# mm16.net
KiCad netlist of a schematic drawn in EAGLE
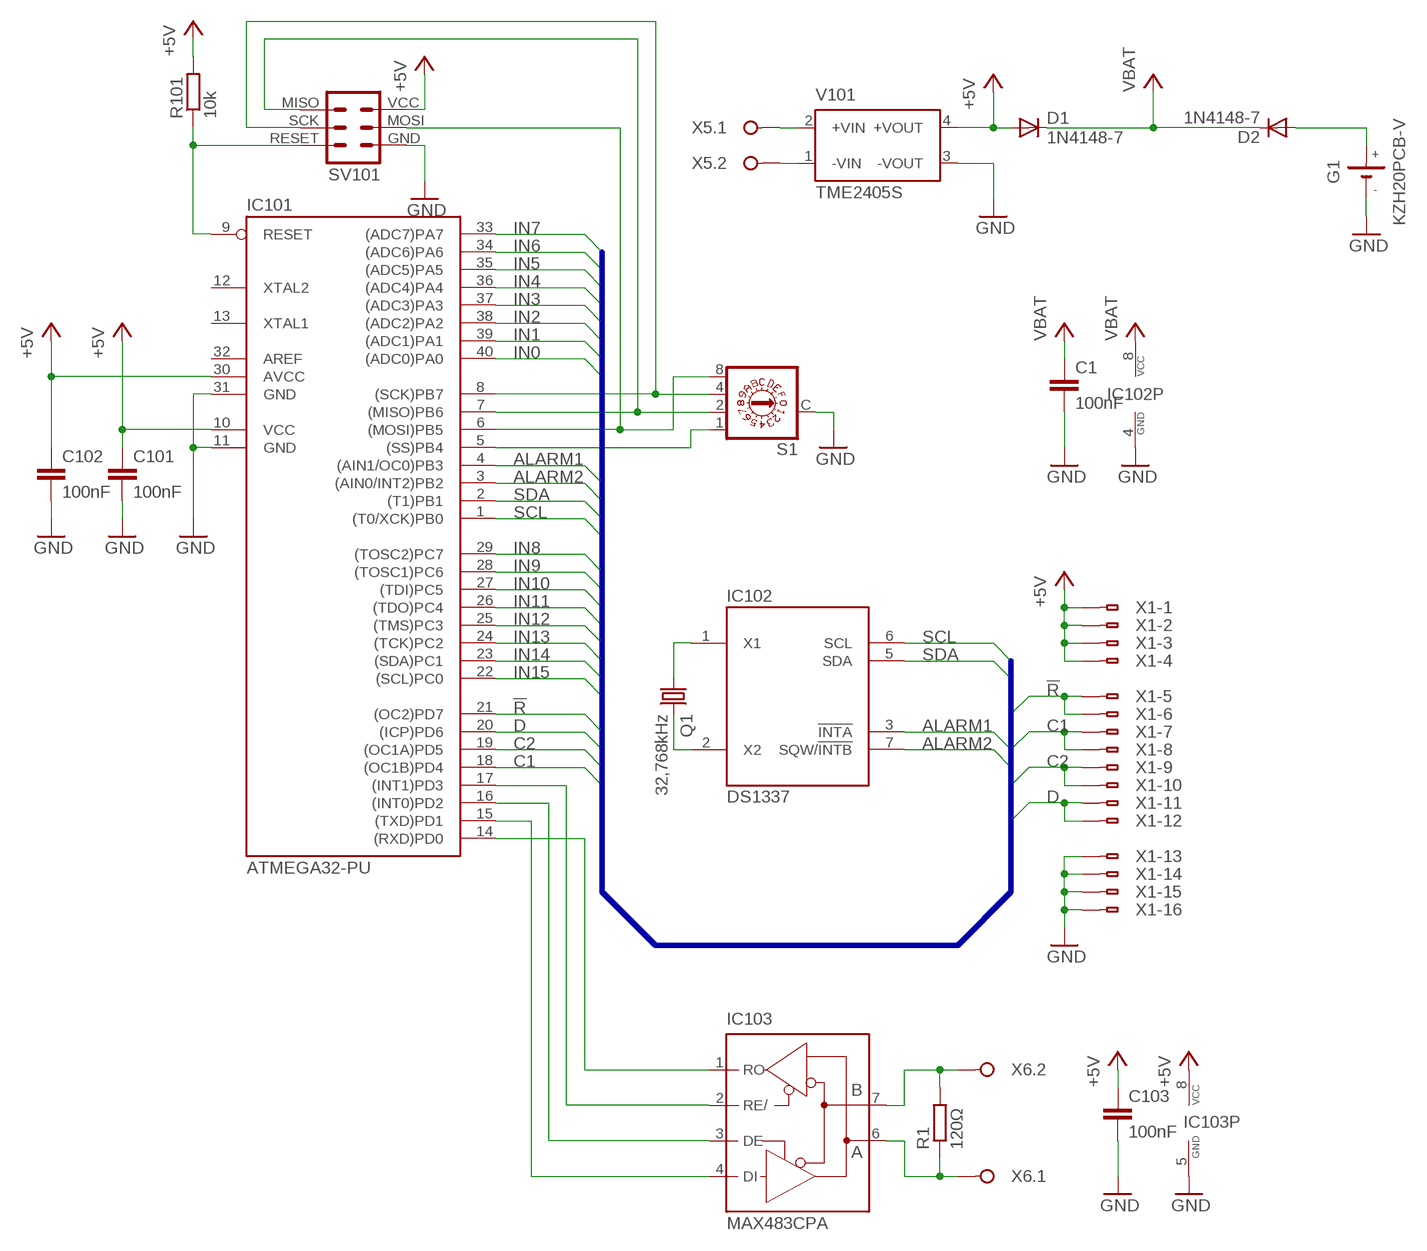
[diagram p0: schematic, sheet 1]
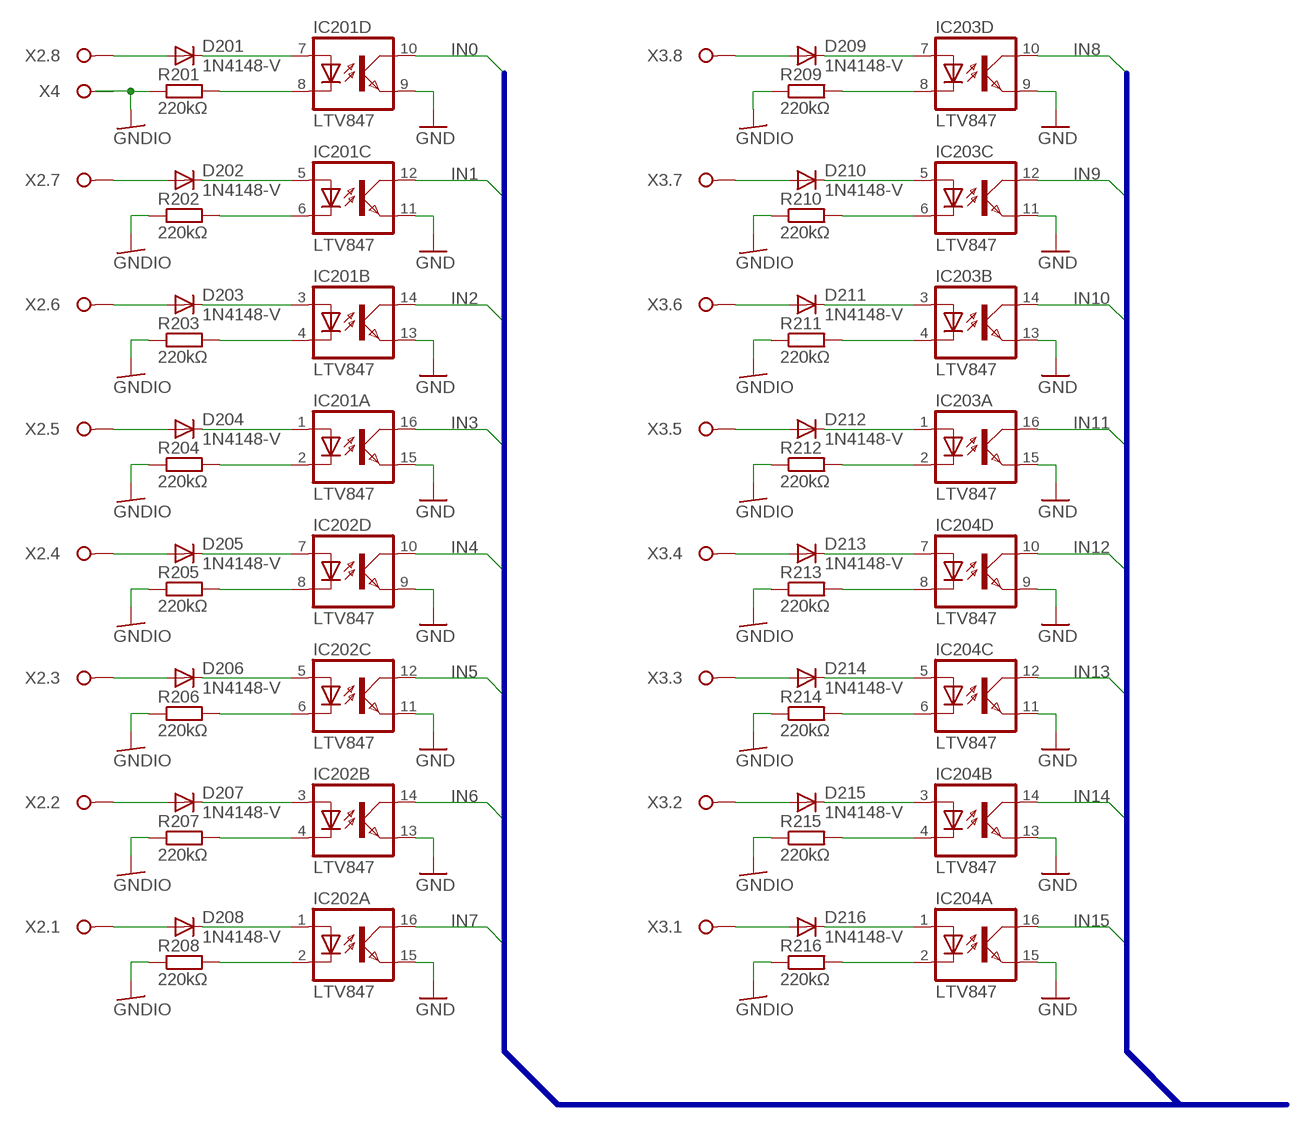
[diagram p1: schematic, sheet 2]

(export (version "E")
  (design (tool "Eeschema 10.0.6"))
  (components
    (comp (ref "D201")
      (value "1N4148-V")
      (footprint "eagle-import:DO35-V")
      (libsource (lib "eagle-import") (part "1N4148-V"))
    )
    (comp (ref "D202")
      (value "1N4148-V")
      (footprint "eagle-import:DO35-V")
      (libsource (lib "eagle-import") (part "1N4148-V"))
    )
    (comp (ref "D203")
      (value "1N4148-V")
      (footprint "eagle-import:DO35-V")
      (libsource (lib "eagle-import") (part "1N4148-V"))
    )
    (comp (ref "D204")
      (value "1N4148-V")
      (footprint "eagle-import:DO35-V")
      (libsource (lib "eagle-import") (part "1N4148-V"))
    )
    (comp (ref "D205")
      (value "1N4148-V")
      (footprint "eagle-import:DO35-V")
      (libsource (lib "eagle-import") (part "1N4148-V"))
    )
    (comp (ref "D206")
      (value "1N4148-V")
      (footprint "eagle-import:DO35-V")
      (libsource (lib "eagle-import") (part "1N4148-V"))
    )
    (comp (ref "D207")
      (value "1N4148-V")
      (footprint "eagle-import:DO35-V")
      (libsource (lib "eagle-import") (part "1N4148-V"))
    )
    (comp (ref "D208")
      (value "1N4148-V")
      (footprint "eagle-import:DO35-V")
      (libsource (lib "eagle-import") (part "1N4148-V"))
    )
    (comp (ref "D209")
      (value "1N4148-V")
      (footprint "eagle-import:DO35-V")
      (libsource (lib "eagle-import") (part "1N4148-V"))
    )
    (comp (ref "D210")
      (value "1N4148-V")
      (footprint "eagle-import:DO35-V")
      (libsource (lib "eagle-import") (part "1N4148-V"))
    )
    (comp (ref "D211")
      (value "1N4148-V")
      (footprint "eagle-import:DO35-V")
      (libsource (lib "eagle-import") (part "1N4148-V"))
    )
    (comp (ref "D212")
      (value "1N4148-V")
      (footprint "eagle-import:DO35-V")
      (libsource (lib "eagle-import") (part "1N4148-V"))
    )
    (comp (ref "D213")
      (value "1N4148-V")
      (footprint "eagle-import:DO35-V")
      (libsource (lib "eagle-import") (part "1N4148-V"))
    )
    (comp (ref "D214")
      (value "1N4148-V")
      (footprint "eagle-import:DO35-V")
      (libsource (lib "eagle-import") (part "1N4148-V"))
    )
    (comp (ref "D215")
      (value "1N4148-V")
      (footprint "eagle-import:DO35-V")
      (libsource (lib "eagle-import") (part "1N4148-V"))
    )
    (comp (ref "D216")
      (value "1N4148-V")
      (footprint "eagle-import:DO35-V")
      (libsource (lib "eagle-import") (part "1N4148-V"))
    )
    (comp (ref "IC201")
      (value "LTV847")
      (footprint "eagle-import:DIL16")
      (libsource (lib "eagle-import") (part "LTV847"))
    )
    (comp (ref "IC202")
      (value "LTV847")
      (footprint "eagle-import:DIL16")
      (libsource (lib "eagle-import") (part "LTV847"))
    )
    (comp (ref "IC203")
      (value "LTV847")
      (footprint "eagle-import:DIL16")
      (libsource (lib "eagle-import") (part "LTV847"))
    )
    (comp (ref "IC204")
      (value "LTV847")
      (footprint "eagle-import:DIL16")
      (libsource (lib "eagle-import") (part "LTV847"))
    )
    (comp (ref "R201")
      (value "220kΩ")
      (footprint "eagle-import:0204V")
      (libsource (lib "eagle-import") (part "R_0204/2V"))
    )
    (comp (ref "R202")
      (value "220kΩ")
      (footprint "eagle-import:0204V")
      (libsource (lib "eagle-import") (part "R_0204/2V"))
    )
    (comp (ref "R203")
      (value "220kΩ")
      (footprint "eagle-import:0204V")
      (libsource (lib "eagle-import") (part "R_0204/2V"))
    )
    (comp (ref "R204")
      (value "220kΩ")
      (footprint "eagle-import:0204V")
      (libsource (lib "eagle-import") (part "R_0204/2V"))
    )
    (comp (ref "R205")
      (value "220kΩ")
      (footprint "eagle-import:0204V")
      (libsource (lib "eagle-import") (part "R_0204/2V"))
    )
    (comp (ref "R206")
      (value "220kΩ")
      (footprint "eagle-import:0204V")
      (libsource (lib "eagle-import") (part "R_0204/2V"))
    )
    (comp (ref "R207")
      (value "220kΩ")
      (footprint "eagle-import:0204V")
      (libsource (lib "eagle-import") (part "R_0204/2V"))
    )
    (comp (ref "R208")
      (value "220kΩ")
      (footprint "eagle-import:0204V")
      (libsource (lib "eagle-import") (part "R_0204/2V"))
    )
    (comp (ref "R209")
      (value "220kΩ")
      (footprint "eagle-import:0204V")
      (libsource (lib "eagle-import") (part "R_0204/2V"))
    )
    (comp (ref "R210")
      (value "220kΩ")
      (footprint "eagle-import:0204V")
      (libsource (lib "eagle-import") (part "R_0204/2V"))
    )
    (comp (ref "R211")
      (value "220kΩ")
      (footprint "eagle-import:0204V")
      (libsource (lib "eagle-import") (part "R_0204/2V"))
    )
    (comp (ref "R212")
      (value "220kΩ")
      (footprint "eagle-import:0204V")
      (libsource (lib "eagle-import") (part "R_0204/2V"))
    )
    (comp (ref "R213")
      (value "220kΩ")
      (footprint "eagle-import:0204V")
      (libsource (lib "eagle-import") (part "R_0204/2V"))
    )
    (comp (ref "R214")
      (value "220kΩ")
      (footprint "eagle-import:0204V")
      (libsource (lib "eagle-import") (part "R_0204/2V"))
    )
    (comp (ref "R215")
      (value "220kΩ")
      (footprint "eagle-import:0204V")
      (libsource (lib "eagle-import") (part "R_0204/2V"))
    )
    (comp (ref "R216")
      (value "220kΩ")
      (footprint "eagle-import:0204V")
      (libsource (lib "eagle-import") (part "R_0204/2V"))
    )
    (comp (ref "X2")
      (value "WAGO_236-408")
      (footprint "eagle-import:WAGO_236-408")
      (libsource (lib "eagle-import") (part "WAGO_236-408"))
    )
    (comp (ref "X3")
      (value "WAGO_236-408")
      (footprint "eagle-import:WAGO_236-408")
      (libsource (lib "eagle-import") (part "WAGO_236-408"))
    )
    (comp (ref "X4")
      (value "WAGO_236-401")
      (footprint "eagle-import:WAGO_236-401")
      (libsource (lib "eagle-import") (part "WAGO_236-401"))
    )
    (comp (ref "C1")
      (value "100nF")
      (footprint "eagle-import:C025-025X050")
      (libsource (lib "eagle-import") (part "C_025-025X050"))
    )
    (comp (ref "C101")
      (value "100nF")
      (footprint "eagle-import:C025-025X050")
      (libsource (lib "eagle-import") (part "C_025-025X050"))
    )
    (comp (ref "C102")
      (value "100nF")
      (footprint "eagle-import:C025-025X050")
      (libsource (lib "eagle-import") (part "C_025-025X050"))
    )
    (comp (ref "C103")
      (value "100nF")
      (footprint "eagle-import:C025-025X050")
      (libsource (lib "eagle-import") (part "C_025-025X050"))
    )
    (comp (ref "D1")
      (value "1N4148-7")
      (footprint "eagle-import:DO35-7")
      (libsource (lib "eagle-import") (part "1N4148-7"))
    )
    (comp (ref "D2")
      (value "1N4148-7")
      (footprint "eagle-import:DO35-7")
      (libsource (lib "eagle-import") (part "1N4148-7"))
    )
    (comp (ref "G1")
      (value "KZH20PCB-V")
      (footprint "eagle-import:KZH20PCB-V")
      (libsource (lib "eagle-import") (part "KZH20PCB-V"))
    )
    (comp (ref "IC101")
      (value "ATMEGA32-PU")
      (footprint "eagle-import:DIL40")
      (libsource (lib "eagle-import") (part "ATMEGA32-PU"))
    )
    (comp (ref "IC102")
      (value "DS1337")
      (footprint "eagle-import:DIL08")
      (libsource (lib "eagle-import") (part "DS1337"))
    )
    (comp (ref "IC103")
      (value "MAX483CPA")
      (footprint "eagle-import:DIL08")
      (libsource (lib "eagle-import") (part "MAX48CPA3"))
    )
    (comp (ref "Q1")
      (value "32,768kHz")
      (footprint "eagle-import:TC38H")
      (libsource (lib "eagle-import") (part "Q_TC38H"))
    )
    (comp (ref "R1")
      (value "120Ω")
      (footprint "eagle-import:0204V")
      (libsource (lib "eagle-import") (part "R_0204/2V"))
    )
    (comp (ref "R101")
      (value "10k")
      (footprint "eagle-import:0204V")
      (libsource (lib "eagle-import") (part "R_0204/2V"))
    )
    (comp (ref "S1")
      (value "P103")
      (footprint "eagle-import:P103")
      (libsource (lib "eagle-import") (part "P103"))
    )
    (comp (ref "SV101")
      (value "AVR_ISP6")
      (footprint "eagle-import:ML6")
      (libsource (lib "eagle-import") (part "AVR_ISP6"))
    )
    (comp (ref "V101")
      (value "TME2405S")
      (footprint "eagle-import:TME-24V")
      (fields
        (field (name "MPN") "TME 2405S")
        (field (name "MPN_1") "TME 2405S")
        (field (name "OC_FARNELL") "1007547")
        (field (name "OC_NEWARK") "51R5329")
      )
      (libsource (lib "eagle-import") (part "TME?2405S"))
    )
    (comp (ref "X1")
      (value "WS16V")
      (footprint "eagle-import:WS16V")
      (libsource (lib "eagle-import") (part "WS16V"))
    )
    (comp (ref "X5")
      (value "WAGO_236-402")
      (footprint "eagle-import:WAGO_236-402")
      (libsource (lib "eagle-import") (part "WAGO_236-402"))
    )
    (comp (ref "X6")
      (value "WAGO_236-402")
      (footprint "eagle-import:WAGO_236-402")
      (libsource (lib "eagle-import") (part "WAGO_236-402"))
    )
  )
  (nets
    (net (code "1") (name "+5V") (class "Default")
      (node (ref "C101") (pin "1") (pinfunction "1_1") (pintype "passive"))
      (node (ref "C102") (pin "1") (pinfunction "1_1") (pintype "passive"))
      (node (ref "C103") (pin "1") (pinfunction "1_1") (pintype "passive"))
      (node (ref "D1") (pin "A") (pinfunction "A_A") (pintype "passive"))
      (node (ref "IC101") (pin "10") (pinfunction "VCC_10") (pintype "power_in"))
      (node (ref "IC101") (pin "30") (pinfunction "AVCC_30") (pintype "power_in"))
      (node (ref "IC103") (pin "8") (pinfunction "VCC_8") (pintype "power_in"))
      (node (ref "R101") (pin "2") (pinfunction "2_2") (pintype "passive"))
      (node (ref "SV101") (pin "VCC") (pinfunction "VCC_VCC") (pintype "passive"))
      (node (ref "V101") (pin "4") (pinfunction "+VOUT_4") (pintype "passive"))
      (node (ref "X1") (pin "1") (pinfunction "A_1") (pintype "passive"))
      (node (ref "X1") (pin "2") (pinfunction "A_2") (pintype "passive"))
      (node (ref "X1") (pin "3") (pinfunction "A_3") (pintype "passive"))
      (node (ref "X1") (pin "4") (pinfunction "A_4") (pintype "passive"))
    )
    (net (code "2") (name "ALARM1") (class "Default")
      (node (ref "IC101") (pin "4") (pinfunction "(AIN1/OC0)PB3_4") (pintype "bidirectional"))
      (node (ref "IC102") (pin "3") (pinfunction "~{INTA}_3") (pintype "open_collector"))
    )
    (net (code "3") (name "ALARM2") (class "Default")
      (node (ref "IC101") (pin "3") (pinfunction "(AIN0/INT2)PB2_3") (pintype "bidirectional"))
      (node (ref "IC102") (pin "7") (pinfunction "SQW/~{INTB}_7") (pintype "open_collector"))
    )
    (net (code "4") (name "C1") (class "Default")
      (node (ref "IC101") (pin "18") (pinfunction "(OC1B)PD4_18") (pintype "bidirectional"))
      (node (ref "X1") (pin "7") (pinfunction "A_7") (pintype "passive"))
      (node (ref "X1") (pin "8") (pinfunction "A_8") (pintype "passive"))
    )
    (net (code "5") (name "C2") (class "Default")
      (node (ref "IC101") (pin "19") (pinfunction "(OC1A)PD5_19") (pintype "bidirectional"))
      (node (ref "X1") (pin "10") (pinfunction "A_10") (pintype "passive"))
      (node (ref "X1") (pin "9") (pinfunction "A_9") (pintype "passive"))
    )
    (net (code "6") (name "D") (class "Default")
      (node (ref "IC101") (pin "20") (pinfunction "(ICP)PD6_20") (pintype "bidirectional"))
      (node (ref "X1") (pin "11") (pinfunction "A_11") (pintype "passive"))
      (node (ref "X1") (pin "12") (pinfunction "A_12") (pintype "passive"))
    )
    (net (code "7") (name "GND") (class "Default")
      (node (ref "C1") (pin "2") (pinfunction "2_2") (pintype "passive"))
      (node (ref "C101") (pin "2") (pinfunction "2_2") (pintype "passive"))
      (node (ref "C102") (pin "2") (pinfunction "2_2") (pintype "passive"))
      (node (ref "C103") (pin "2") (pinfunction "2_2") (pintype "passive"))
      (node (ref "G1") (pin "-") (pinfunction "-_-") (pintype "passive"))
      (node (ref "IC101") (pin "11") (pinfunction "GND_11") (pintype "power_in"))
      (node (ref "IC101") (pin "31") (pinfunction "GND_31") (pintype "power_in"))
      (node (ref "IC102") (pin "4") (pinfunction "GND_4") (pintype "power_in"))
      (node (ref "IC103") (pin "5") (pinfunction "GND_5") (pintype "power_in"))
      (node (ref "IC201") (pin "11") (pinfunction "EMIT_11") (pintype "passive"))
      (node (ref "IC201") (pin "13") (pinfunction "EMIT_13") (pintype "passive"))
      (node (ref "IC201") (pin "15") (pinfunction "EMIT_15") (pintype "passive"))
      (node (ref "IC201") (pin "9") (pinfunction "EMIT_9") (pintype "passive"))
      (node (ref "IC202") (pin "11") (pinfunction "EMIT_11") (pintype "passive"))
      (node (ref "IC202") (pin "13") (pinfunction "EMIT_13") (pintype "passive"))
      (node (ref "IC202") (pin "15") (pinfunction "EMIT_15") (pintype "passive"))
      (node (ref "IC202") (pin "9") (pinfunction "EMIT_9") (pintype "passive"))
      (node (ref "IC203") (pin "11") (pinfunction "EMIT_11") (pintype "passive"))
      (node (ref "IC203") (pin "13") (pinfunction "EMIT_13") (pintype "passive"))
      (node (ref "IC203") (pin "15") (pinfunction "EMIT_15") (pintype "passive"))
      (node (ref "IC203") (pin "9") (pinfunction "EMIT_9") (pintype "passive"))
      (node (ref "IC204") (pin "11") (pinfunction "EMIT_11") (pintype "passive"))
      (node (ref "IC204") (pin "13") (pinfunction "EMIT_13") (pintype "passive"))
      (node (ref "IC204") (pin "15") (pinfunction "EMIT_15") (pintype "passive"))
      (node (ref "IC204") (pin "9") (pinfunction "EMIT_9") (pintype "passive"))
      (node (ref "S1") (pin "C") (pinfunction "C_C") (pintype "passive"))
      (node (ref "SV101") (pin "GND") (pinfunction "GND_GND") (pintype "passive"))
      (node (ref "V101") (pin "3") (pinfunction "-VOUT_3") (pintype "passive"))
      (node (ref "X1") (pin "13") (pinfunction "A_13") (pintype "passive"))
      (node (ref "X1") (pin "14") (pinfunction "A_14") (pintype "passive"))
      (node (ref "X1") (pin "15") (pinfunction "A_15") (pintype "passive"))
      (node (ref "X1") (pin "16") (pinfunction "A_16") (pintype "passive"))
    )
    (net (code "8") (name "GNDIO") (class "Default")
      (node (ref "R201") (pin "1") (pinfunction "1_1") (pintype "passive"))
      (node (ref "R202") (pin "1") (pinfunction "1_1") (pintype "passive"))
      (node (ref "R203") (pin "1") (pinfunction "1_1") (pintype "passive"))
      (node (ref "R204") (pin "1") (pinfunction "1_1") (pintype "passive"))
      (node (ref "R205") (pin "1") (pinfunction "1_1") (pintype "passive"))
      (node (ref "R206") (pin "1") (pinfunction "1_1") (pintype "passive"))
      (node (ref "R207") (pin "1") (pinfunction "1_1") (pintype "passive"))
      (node (ref "R208") (pin "1") (pinfunction "1_1") (pintype "passive"))
      (node (ref "R209") (pin "1") (pinfunction "1_1") (pintype "passive"))
      (node (ref "R210") (pin "1") (pinfunction "1_1") (pintype "passive"))
      (node (ref "R211") (pin "1") (pinfunction "1_1") (pintype "passive"))
      (node (ref "R212") (pin "1") (pinfunction "1_1") (pintype "passive"))
      (node (ref "R213") (pin "1") (pinfunction "1_1") (pintype "passive"))
      (node (ref "R214") (pin "1") (pinfunction "1_1") (pintype "passive"))
      (node (ref "R215") (pin "1") (pinfunction "1_1") (pintype "passive"))
      (node (ref "R216") (pin "1") (pinfunction "1_1") (pintype "passive"))
      (node (ref "X4") (pin "A1") (pinfunction "A_A1") (pintype "passive"))
      (node (ref "X4") (pin "B1") (pinfunction "B_B1") (pintype "passive"))
    )
    (net (code "9") (name "IN0") (class "Default")
      (node (ref "IC101") (pin "40") (pinfunction "(ADC0)PA0_40") (pintype "bidirectional"))
      (node (ref "IC201") (pin "10") (pinfunction "COL_10") (pintype "passive"))
    )
    (net (code "10") (name "IN1") (class "Default")
      (node (ref "IC101") (pin "39") (pinfunction "(ADC1)PA1_39") (pintype "bidirectional"))
      (node (ref "IC201") (pin "12") (pinfunction "COL_12") (pintype "passive"))
    )
    (net (code "11") (name "IN2") (class "Default")
      (node (ref "IC101") (pin "38") (pinfunction "(ADC2)PA2_38") (pintype "bidirectional"))
      (node (ref "IC201") (pin "14") (pinfunction "COL_14") (pintype "passive"))
    )
    (net (code "12") (name "IN3") (class "Default")
      (node (ref "IC101") (pin "37") (pinfunction "(ADC3)PA3_37") (pintype "bidirectional"))
      (node (ref "IC201") (pin "16") (pinfunction "COL_16") (pintype "passive"))
    )
    (net (code "13") (name "IN4") (class "Default")
      (node (ref "IC101") (pin "36") (pinfunction "(ADC4)PA4_36") (pintype "bidirectional"))
      (node (ref "IC202") (pin "10") (pinfunction "COL_10") (pintype "passive"))
    )
    (net (code "14") (name "IN5") (class "Default")
      (node (ref "IC101") (pin "35") (pinfunction "(ADC5)PA5_35") (pintype "bidirectional"))
      (node (ref "IC202") (pin "12") (pinfunction "COL_12") (pintype "passive"))
    )
    (net (code "15") (name "IN6") (class "Default")
      (node (ref "IC101") (pin "34") (pinfunction "(ADC6)PA6_34") (pintype "bidirectional"))
      (node (ref "IC202") (pin "14") (pinfunction "COL_14") (pintype "passive"))
    )
    (net (code "16") (name "IN7") (class "Default")
      (node (ref "IC101") (pin "33") (pinfunction "(ADC7)PA7_33") (pintype "bidirectional"))
      (node (ref "IC202") (pin "16") (pinfunction "COL_16") (pintype "passive"))
    )
    (net (code "17") (name "IN8") (class "Default")
      (node (ref "IC101") (pin "29") (pinfunction "(TOSC2)PC7_29") (pintype "bidirectional"))
      (node (ref "IC203") (pin "10") (pinfunction "COL_10") (pintype "passive"))
    )
    (net (code "18") (name "IN9") (class "Default")
      (node (ref "IC101") (pin "28") (pinfunction "(TOSC1)PC6_28") (pintype "bidirectional"))
      (node (ref "IC203") (pin "12") (pinfunction "COL_12") (pintype "passive"))
    )
    (net (code "19") (name "IN10") (class "Default")
      (node (ref "IC101") (pin "27") (pinfunction "(TDI)PC5_27") (pintype "bidirectional"))
      (node (ref "IC203") (pin "14") (pinfunction "COL_14") (pintype "passive"))
    )
    (net (code "20") (name "IN11") (class "Default")
      (node (ref "IC101") (pin "26") (pinfunction "(TDO)PC4_26") (pintype "bidirectional"))
      (node (ref "IC203") (pin "16") (pinfunction "COL_16") (pintype "passive"))
    )
    (net (code "21") (name "IN12") (class "Default")
      (node (ref "IC101") (pin "25") (pinfunction "(TMS)PC3_25") (pintype "bidirectional"))
      (node (ref "IC204") (pin "10") (pinfunction "COL_10") (pintype "passive"))
    )
    (net (code "22") (name "IN13") (class "Default")
      (node (ref "IC101") (pin "24") (pinfunction "(TCK)PC2_24") (pintype "bidirectional"))
      (node (ref "IC204") (pin "12") (pinfunction "COL_12") (pintype "passive"))
    )
    (net (code "23") (name "IN14") (class "Default")
      (node (ref "IC101") (pin "23") (pinfunction "(SDA)PC1_23") (pintype "bidirectional"))
      (node (ref "IC204") (pin "14") (pinfunction "COL_14") (pintype "passive"))
    )
    (net (code "24") (name "IN15") (class "Default")
      (node (ref "IC101") (pin "22") (pinfunction "(SCL)PC0_22") (pintype "bidirectional"))
      (node (ref "IC204") (pin "16") (pinfunction "COL_16") (pintype "passive"))
    )
    (net (code "25") (name "Net-(D2-PadA)") (class "Default")
      (node (ref "D2") (pin "A") (pinfunction "A_A") (pintype "passive"))
      (node (ref "G1") (pin "+1") (pinfunction "+_+1") (pintype "passive"))
      (node (ref "G1") (pin "+2") (pinfunction "+_+2") (pintype "passive"))
    )
    (net (code "26") (name "Net-(D201-A)") (class "Default")
      (node (ref "D201") (pin "1") (pinfunction "A_1") (pintype "passive"))
      (node (ref "X2") (pin "A8") (pinfunction "A_A8") (pintype "passive"))
      (node (ref "X2") (pin "B8") (pinfunction "A_B8") (pintype "passive"))
    )
    (net (code "27") (name "Net-(D201-C)") (class "Default")
      (node (ref "D201") (pin "2") (pinfunction "C_2") (pintype "passive"))
      (node (ref "IC201") (pin "7") (pinfunction "A_7") (pintype "passive"))
    )
    (net (code "28") (name "Net-(D202-A)") (class "Default")
      (node (ref "D202") (pin "1") (pinfunction "A_1") (pintype "passive"))
      (node (ref "X2") (pin "A7") (pinfunction "A_A7") (pintype "passive"))
      (node (ref "X2") (pin "B7") (pinfunction "A_B7") (pintype "passive"))
    )
    (net (code "29") (name "Net-(D202-C)") (class "Default")
      (node (ref "D202") (pin "2") (pinfunction "C_2") (pintype "passive"))
      (node (ref "IC201") (pin "5") (pinfunction "A_5") (pintype "passive"))
    )
    (net (code "30") (name "Net-(D203-A)") (class "Default")
      (node (ref "D203") (pin "1") (pinfunction "A_1") (pintype "passive"))
      (node (ref "X2") (pin "A6") (pinfunction "A_A6") (pintype "passive"))
      (node (ref "X2") (pin "B6") (pinfunction "A_B6") (pintype "passive"))
    )
    (net (code "31") (name "Net-(D203-C)") (class "Default")
      (node (ref "D203") (pin "2") (pinfunction "C_2") (pintype "passive"))
      (node (ref "IC201") (pin "3") (pinfunction "A_3") (pintype "passive"))
    )
    (net (code "32") (name "Net-(D204-A)") (class "Default")
      (node (ref "D204") (pin "1") (pinfunction "A_1") (pintype "passive"))
      (node (ref "X2") (pin "A5") (pinfunction "A_A5") (pintype "passive"))
      (node (ref "X2") (pin "B5") (pinfunction "A_B5") (pintype "passive"))
    )
    (net (code "33") (name "Net-(D204-C)") (class "Default")
      (node (ref "D204") (pin "2") (pinfunction "C_2") (pintype "passive"))
      (node (ref "IC201") (pin "1") (pinfunction "A_1") (pintype "passive"))
    )
    (net (code "34") (name "Net-(D205-A)") (class "Default")
      (node (ref "D205") (pin "1") (pinfunction "A_1") (pintype "passive"))
      (node (ref "X2") (pin "A4") (pinfunction "A_A4") (pintype "passive"))
      (node (ref "X2") (pin "B4") (pinfunction "A_B4") (pintype "passive"))
    )
    (net (code "35") (name "Net-(D205-C)") (class "Default")
      (node (ref "D205") (pin "2") (pinfunction "C_2") (pintype "passive"))
      (node (ref "IC202") (pin "7") (pinfunction "A_7") (pintype "passive"))
    )
    (net (code "36") (name "Net-(D206-A)") (class "Default")
      (node (ref "D206") (pin "1") (pinfunction "A_1") (pintype "passive"))
      (node (ref "X2") (pin "A3") (pinfunction "A_A3") (pintype "passive"))
      (node (ref "X2") (pin "B3") (pinfunction "A_B3") (pintype "passive"))
    )
    (net (code "37") (name "Net-(D206-C)") (class "Default")
      (node (ref "D206") (pin "2") (pinfunction "C_2") (pintype "passive"))
      (node (ref "IC202") (pin "5") (pinfunction "A_5") (pintype "passive"))
    )
    (net (code "38") (name "Net-(D207-A)") (class "Default")
      (node (ref "D207") (pin "1") (pinfunction "A_1") (pintype "passive"))
      (node (ref "X2") (pin "A2") (pinfunction "A_A2") (pintype "passive"))
      (node (ref "X2") (pin "B2") (pinfunction "A_B2") (pintype "passive"))
    )
    (net (code "39") (name "Net-(D207-C)") (class "Default")
      (node (ref "D207") (pin "2") (pinfunction "C_2") (pintype "passive"))
      (node (ref "IC202") (pin "3") (pinfunction "A_3") (pintype "passive"))
    )
    (net (code "40") (name "Net-(D208-A)") (class "Default")
      (node (ref "D208") (pin "1") (pinfunction "A_1") (pintype "passive"))
      (node (ref "X2") (pin "A1") (pinfunction "A_A1") (pintype "passive"))
      (node (ref "X2") (pin "B1") (pinfunction "A_B1") (pintype "passive"))
    )
    (net (code "41") (name "Net-(D208-C)") (class "Default")
      (node (ref "D208") (pin "2") (pinfunction "C_2") (pintype "passive"))
      (node (ref "IC202") (pin "1") (pinfunction "A_1") (pintype "passive"))
    )
    (net (code "42") (name "Net-(D209-A)") (class "Default")
      (node (ref "D209") (pin "1") (pinfunction "A_1") (pintype "passive"))
      (node (ref "X3") (pin "A8") (pinfunction "A_A8") (pintype "passive"))
      (node (ref "X3") (pin "B8") (pinfunction "A_B8") (pintype "passive"))
    )
    (net (code "43") (name "Net-(D209-C)") (class "Default")
      (node (ref "D209") (pin "2") (pinfunction "C_2") (pintype "passive"))
      (node (ref "IC203") (pin "7") (pinfunction "A_7") (pintype "passive"))
    )
    (net (code "44") (name "Net-(D210-A)") (class "Default")
      (node (ref "D210") (pin "1") (pinfunction "A_1") (pintype "passive"))
      (node (ref "X3") (pin "A7") (pinfunction "A_A7") (pintype "passive"))
      (node (ref "X3") (pin "B7") (pinfunction "A_B7") (pintype "passive"))
    )
    (net (code "45") (name "Net-(D210-C)") (class "Default")
      (node (ref "D210") (pin "2") (pinfunction "C_2") (pintype "passive"))
      (node (ref "IC203") (pin "5") (pinfunction "A_5") (pintype "passive"))
    )
    (net (code "46") (name "Net-(D211-A)") (class "Default")
      (node (ref "D211") (pin "1") (pinfunction "A_1") (pintype "passive"))
      (node (ref "X3") (pin "A6") (pinfunction "A_A6") (pintype "passive"))
      (node (ref "X3") (pin "B6") (pinfunction "A_B6") (pintype "passive"))
    )
    (net (code "47") (name "Net-(D211-C)") (class "Default")
      (node (ref "D211") (pin "2") (pinfunction "C_2") (pintype "passive"))
      (node (ref "IC203") (pin "3") (pinfunction "A_3") (pintype "passive"))
    )
    (net (code "48") (name "Net-(D212-A)") (class "Default")
      (node (ref "D212") (pin "1") (pinfunction "A_1") (pintype "passive"))
      (node (ref "X3") (pin "A5") (pinfunction "A_A5") (pintype "passive"))
      (node (ref "X3") (pin "B5") (pinfunction "A_B5") (pintype "passive"))
    )
    (net (code "49") (name "Net-(D212-C)") (class "Default")
      (node (ref "D212") (pin "2") (pinfunction "C_2") (pintype "passive"))
      (node (ref "IC203") (pin "1") (pinfunction "A_1") (pintype "passive"))
    )
    (net (code "50") (name "Net-(D213-A)") (class "Default")
      (node (ref "D213") (pin "1") (pinfunction "A_1") (pintype "passive"))
      (node (ref "X3") (pin "A4") (pinfunction "A_A4") (pintype "passive"))
      (node (ref "X3") (pin "B4") (pinfunction "A_B4") (pintype "passive"))
    )
    (net (code "51") (name "Net-(D213-C)") (class "Default")
      (node (ref "D213") (pin "2") (pinfunction "C_2") (pintype "passive"))
      (node (ref "IC204") (pin "7") (pinfunction "A_7") (pintype "passive"))
    )
    (net (code "52") (name "Net-(D214-A)") (class "Default")
      (node (ref "D214") (pin "1") (pinfunction "A_1") (pintype "passive"))
      (node (ref "X3") (pin "A3") (pinfunction "A_A3") (pintype "passive"))
      (node (ref "X3") (pin "B3") (pinfunction "A_B3") (pintype "passive"))
    )
    (net (code "53") (name "Net-(D214-C)") (class "Default")
      (node (ref "D214") (pin "2") (pinfunction "C_2") (pintype "passive"))
      (node (ref "IC204") (pin "5") (pinfunction "A_5") (pintype "passive"))
    )
    (net (code "54") (name "Net-(D215-A)") (class "Default")
      (node (ref "D215") (pin "1") (pinfunction "A_1") (pintype "passive"))
      (node (ref "X3") (pin "A2") (pinfunction "A_A2") (pintype "passive"))
      (node (ref "X3") (pin "B2") (pinfunction "A_B2") (pintype "passive"))
    )
    (net (code "55") (name "Net-(D215-C)") (class "Default")
      (node (ref "D215") (pin "2") (pinfunction "C_2") (pintype "passive"))
      (node (ref "IC204") (pin "3") (pinfunction "A_3") (pintype "passive"))
    )
    (net (code "56") (name "Net-(D216-A)") (class "Default")
      (node (ref "D216") (pin "1") (pinfunction "A_1") (pintype "passive"))
      (node (ref "X3") (pin "A1") (pinfunction "A_A1") (pintype "passive"))
      (node (ref "X3") (pin "B1") (pinfunction "A_B1") (pintype "passive"))
    )
    (net (code "57") (name "Net-(D216-C)") (class "Default")
      (node (ref "D216") (pin "2") (pinfunction "C_2") (pintype "passive"))
      (node (ref "IC204") (pin "1") (pinfunction "A_1") (pintype "passive"))
    )
    (net (code "58") (name "Net-(IC101-(INT0)PD2)") (class "Default")
      (node (ref "IC101") (pin "16") (pinfunction "(INT0)PD2_16") (pintype "bidirectional"))
      (node (ref "IC103") (pin "3") (pinfunction "DE_3") (pintype "input"))
    )
    (net (code "59") (name "Net-(IC101-(INT1)PD3)") (class "Default")
      (node (ref "IC101") (pin "17") (pinfunction "(INT1)PD3_17") (pintype "bidirectional"))
      (node (ref "IC103") (pin "2") (pinfunction "RE/_2") (pintype "input"))
    )
    (net (code "60") (name "Net-(IC101-(MISO)PB6)") (class "Default")
      (node (ref "IC101") (pin "7") (pinfunction "(MISO)PB6_7") (pintype "bidirectional"))
      (node (ref "S1") (pin "2") (pinfunction "2_2") (pintype "passive"))
      (node (ref "SV101") (pin "MISO") (pinfunction "MISO_MISO") (pintype "passive"))
    )
    (net (code "61") (name "Net-(IC101-(MOSI)PB5)") (class "Default")
      (node (ref "IC101") (pin "6") (pinfunction "(MOSI)PB5_6") (pintype "bidirectional"))
      (node (ref "S1") (pin "8") (pinfunction "8_8") (pintype "passive"))
      (node (ref "SV101") (pin "MOSI") (pinfunction "MOSI_MOSI") (pintype "passive"))
    )
    (net (code "62") (name "Net-(IC101-(RXD)PD0)") (class "Default")
      (node (ref "IC101") (pin "14") (pinfunction "(RXD)PD0_14") (pintype "bidirectional"))
      (node (ref "IC103") (pin "1") (pinfunction "RO_1") (pintype "output"))
    )
    (net (code "63") (name "Net-(IC101-(SCK)PB7)") (class "Default")
      (node (ref "IC101") (pin "8") (pinfunction "(SCK)PB7_8") (pintype "bidirectional"))
      (node (ref "S1") (pin "4") (pinfunction "4_4") (pintype "passive"))
      (node (ref "SV101") (pin "SCK") (pinfunction "SCK_SCK") (pintype "passive"))
    )
    (net (code "64") (name "Net-(IC101-(SS)PB4)") (class "Default")
      (node (ref "IC101") (pin "5") (pinfunction "(SS)PB4_5") (pintype "bidirectional"))
      (node (ref "S1") (pin "1") (pinfunction "1_1") (pintype "passive"))
    )
    (net (code "65") (name "Net-(IC101-(TXD)PD1)") (class "Default")
      (node (ref "IC101") (pin "15") (pinfunction "(TXD)PD1_15") (pintype "bidirectional"))
      (node (ref "IC103") (pin "4") (pinfunction "DI_4") (pintype "input"))
    )
    (net (code "66") (name "Net-(IC101-RESET)") (class "Default")
      (node (ref "IC101") (pin "9") (pinfunction "RESET_9") (pintype "input"))
      (node (ref "R101") (pin "1") (pinfunction "1_1") (pintype "passive"))
      (node (ref "SV101") (pin "RESET") (pinfunction "RESET_RESET") (pintype "passive"))
    )
    (net (code "67") (name "Net-(IC102A-X1)") (class "Default")
      (node (ref "IC102") (pin "1") (pinfunction "X1_1") (pintype "bidirectional"))
      (node (ref "Q1") (pin "1") (pinfunction "1_1") (pintype "passive"))
    )
    (net (code "68") (name "Net-(IC102A-X2)") (class "Default")
      (node (ref "IC102") (pin "2") (pinfunction "X2_2") (pintype "bidirectional"))
      (node (ref "Q1") (pin "2") (pinfunction "2_2") (pintype "passive"))
    )
    (net (code "69") (name "Net-(IC103A-A)") (class "Default")
      (node (ref "IC103") (pin "6") (pinfunction "A_6") (pintype "passive"))
      (node (ref "R1") (pin "1") (pinfunction "1_1") (pintype "passive"))
      (node (ref "X6") (pin "A1") (pinfunction "A_A1") (pintype "passive"))
      (node (ref "X6") (pin "B1") (pinfunction "A_B1") (pintype "passive"))
    )
    (net (code "70") (name "Net-(IC103A-B)") (class "Default")
      (node (ref "IC103") (pin "7") (pinfunction "B_7") (pintype "passive"))
      (node (ref "R1") (pin "2") (pinfunction "2_2") (pintype "passive"))
      (node (ref "X6") (pin "A2") (pinfunction "A_A2") (pintype "passive"))
      (node (ref "X6") (pin "B2") (pinfunction "A_B2") (pintype "passive"))
    )
    (net (code "71") (name "Net-(IC201A-C)") (class "Default")
      (node (ref "IC201") (pin "2") (pinfunction "C_2") (pintype "passive"))
      (node (ref "R204") (pin "2") (pinfunction "2_2") (pintype "passive"))
    )
    (net (code "72") (name "Net-(IC201B-C)") (class "Default")
      (node (ref "IC201") (pin "4") (pinfunction "C_4") (pintype "passive"))
      (node (ref "R203") (pin "2") (pinfunction "2_2") (pintype "passive"))
    )
    (net (code "73") (name "Net-(IC201C-C)") (class "Default")
      (node (ref "IC201") (pin "6") (pinfunction "C_6") (pintype "passive"))
      (node (ref "R202") (pin "2") (pinfunction "2_2") (pintype "passive"))
    )
    (net (code "74") (name "Net-(IC201D-C)") (class "Default")
      (node (ref "IC201") (pin "8") (pinfunction "C_8") (pintype "passive"))
      (node (ref "R201") (pin "2") (pinfunction "2_2") (pintype "passive"))
    )
    (net (code "75") (name "Net-(IC202A-C)") (class "Default")
      (node (ref "IC202") (pin "2") (pinfunction "C_2") (pintype "passive"))
      (node (ref "R208") (pin "2") (pinfunction "2_2") (pintype "passive"))
    )
    (net (code "76") (name "Net-(IC202B-C)") (class "Default")
      (node (ref "IC202") (pin "4") (pinfunction "C_4") (pintype "passive"))
      (node (ref "R207") (pin "2") (pinfunction "2_2") (pintype "passive"))
    )
    (net (code "77") (name "Net-(IC202C-C)") (class "Default")
      (node (ref "IC202") (pin "6") (pinfunction "C_6") (pintype "passive"))
      (node (ref "R206") (pin "2") (pinfunction "2_2") (pintype "passive"))
    )
    (net (code "78") (name "Net-(IC202D-C)") (class "Default")
      (node (ref "IC202") (pin "8") (pinfunction "C_8") (pintype "passive"))
      (node (ref "R205") (pin "2") (pinfunction "2_2") (pintype "passive"))
    )
    (net (code "79") (name "Net-(IC203A-C)") (class "Default")
      (node (ref "IC203") (pin "2") (pinfunction "C_2") (pintype "passive"))
      (node (ref "R212") (pin "2") (pinfunction "2_2") (pintype "passive"))
    )
    (net (code "80") (name "Net-(IC203B-C)") (class "Default")
      (node (ref "IC203") (pin "4") (pinfunction "C_4") (pintype "passive"))
      (node (ref "R211") (pin "2") (pinfunction "2_2") (pintype "passive"))
    )
    (net (code "81") (name "Net-(IC203C-C)") (class "Default")
      (node (ref "IC203") (pin "6") (pinfunction "C_6") (pintype "passive"))
      (node (ref "R210") (pin "2") (pinfunction "2_2") (pintype "passive"))
    )
    (net (code "82") (name "Net-(IC203D-C)") (class "Default")
      (node (ref "IC203") (pin "8") (pinfunction "C_8") (pintype "passive"))
      (node (ref "R209") (pin "2") (pinfunction "2_2") (pintype "passive"))
    )
    (net (code "83") (name "Net-(IC204A-C)") (class "Default")
      (node (ref "IC204") (pin "2") (pinfunction "C_2") (pintype "passive"))
      (node (ref "R216") (pin "2") (pinfunction "2_2") (pintype "passive"))
    )
    (net (code "84") (name "Net-(IC204B-C)") (class "Default")
      (node (ref "IC204") (pin "4") (pinfunction "C_4") (pintype "passive"))
      (node (ref "R215") (pin "2") (pinfunction "2_2") (pintype "passive"))
    )
    (net (code "85") (name "Net-(IC204C-C)") (class "Default")
      (node (ref "IC204") (pin "6") (pinfunction "C_6") (pintype "passive"))
      (node (ref "R214") (pin "2") (pinfunction "2_2") (pintype "passive"))
    )
    (net (code "86") (name "Net-(IC204D-C)") (class "Default")
      (node (ref "IC204") (pin "8") (pinfunction "C_8") (pintype "passive"))
      (node (ref "R213") (pin "2") (pinfunction "2_2") (pintype "passive"))
    )
    (net (code "87") (name "Net-(V101-+VIN)") (class "Default")
      (node (ref "V101") (pin "2") (pinfunction "+VIN_2") (pintype "passive"))
      (node (ref "X5") (pin "A1") (pinfunction "A_A1") (pintype "passive"))
      (node (ref "X5") (pin "B1") (pinfunction "A_B1") (pintype "passive"))
    )
    (net (code "88") (name "Net-(V101--VIN)") (class "Default")
      (node (ref "V101") (pin "1") (pinfunction "-VIN_1") (pintype "passive"))
      (node (ref "X5") (pin "A2") (pinfunction "A_A2") (pintype "passive"))
      (node (ref "X5") (pin "B2") (pinfunction "A_B2") (pintype "passive"))
    )
    (net (code "89") (name "SCL") (class "Default")
      (node (ref "IC101") (pin "1") (pinfunction "(T0/XCK)PB0_1") (pintype "bidirectional"))
      (node (ref "IC102") (pin "6") (pinfunction "SCL_6") (pintype "bidirectional"))
    )
    (net (code "90") (name "SDA") (class "Default")
      (node (ref "IC101") (pin "2") (pinfunction "(T1)PB1_2") (pintype "bidirectional"))
      (node (ref "IC102") (pin "5") (pinfunction "SDA_5") (pintype "bidirectional"))
    )
    (net (code "91") (name "VCC") (class "Default")
      (node (ref "C1") (pin "1") (pinfunction "1_1") (pintype "passive"))
      (node (ref "D1") (pin "C") (pinfunction "C_C") (pintype "passive"))
      (node (ref "D2") (pin "C") (pinfunction "C_C") (pintype "passive"))
      (node (ref "IC102") (pin "8") (pinfunction "VCC_8") (pintype "power_in"))
    )
    (net (code "92") (name "unconnected-(IC101-AREF-Pad32)") (class "Default")
      (node (ref "IC101") (pin "32") (pinfunction "AREF_32") (pintype "passive"))
    )
    (net (code "93") (name "unconnected-(IC101-XTAL1-Pad13)") (class "Default")
      (node (ref "IC101") (pin "13") (pinfunction "XTAL1_13") (pintype "bidirectional"))
    )
    (net (code "94") (name "unconnected-(IC101-XTAL2-Pad12)") (class "Default")
      (node (ref "IC101") (pin "12") (pinfunction "XTAL2_12") (pintype "bidirectional"))
    )
    (net (code "95") (name "~{R}") (class "Default")
      (node (ref "IC101") (pin "21") (pinfunction "(OC2)PD7_21") (pintype "bidirectional"))
      (node (ref "X1") (pin "5") (pinfunction "A_5") (pintype "passive"))
      (node (ref "X1") (pin "6") (pinfunction "A_6") (pintype "passive"))
    )
  )
)
